# Adafruit_IS31FL3731_STEMMA_QT.net
KiCad netlist of a schematic drawn in EAGLE
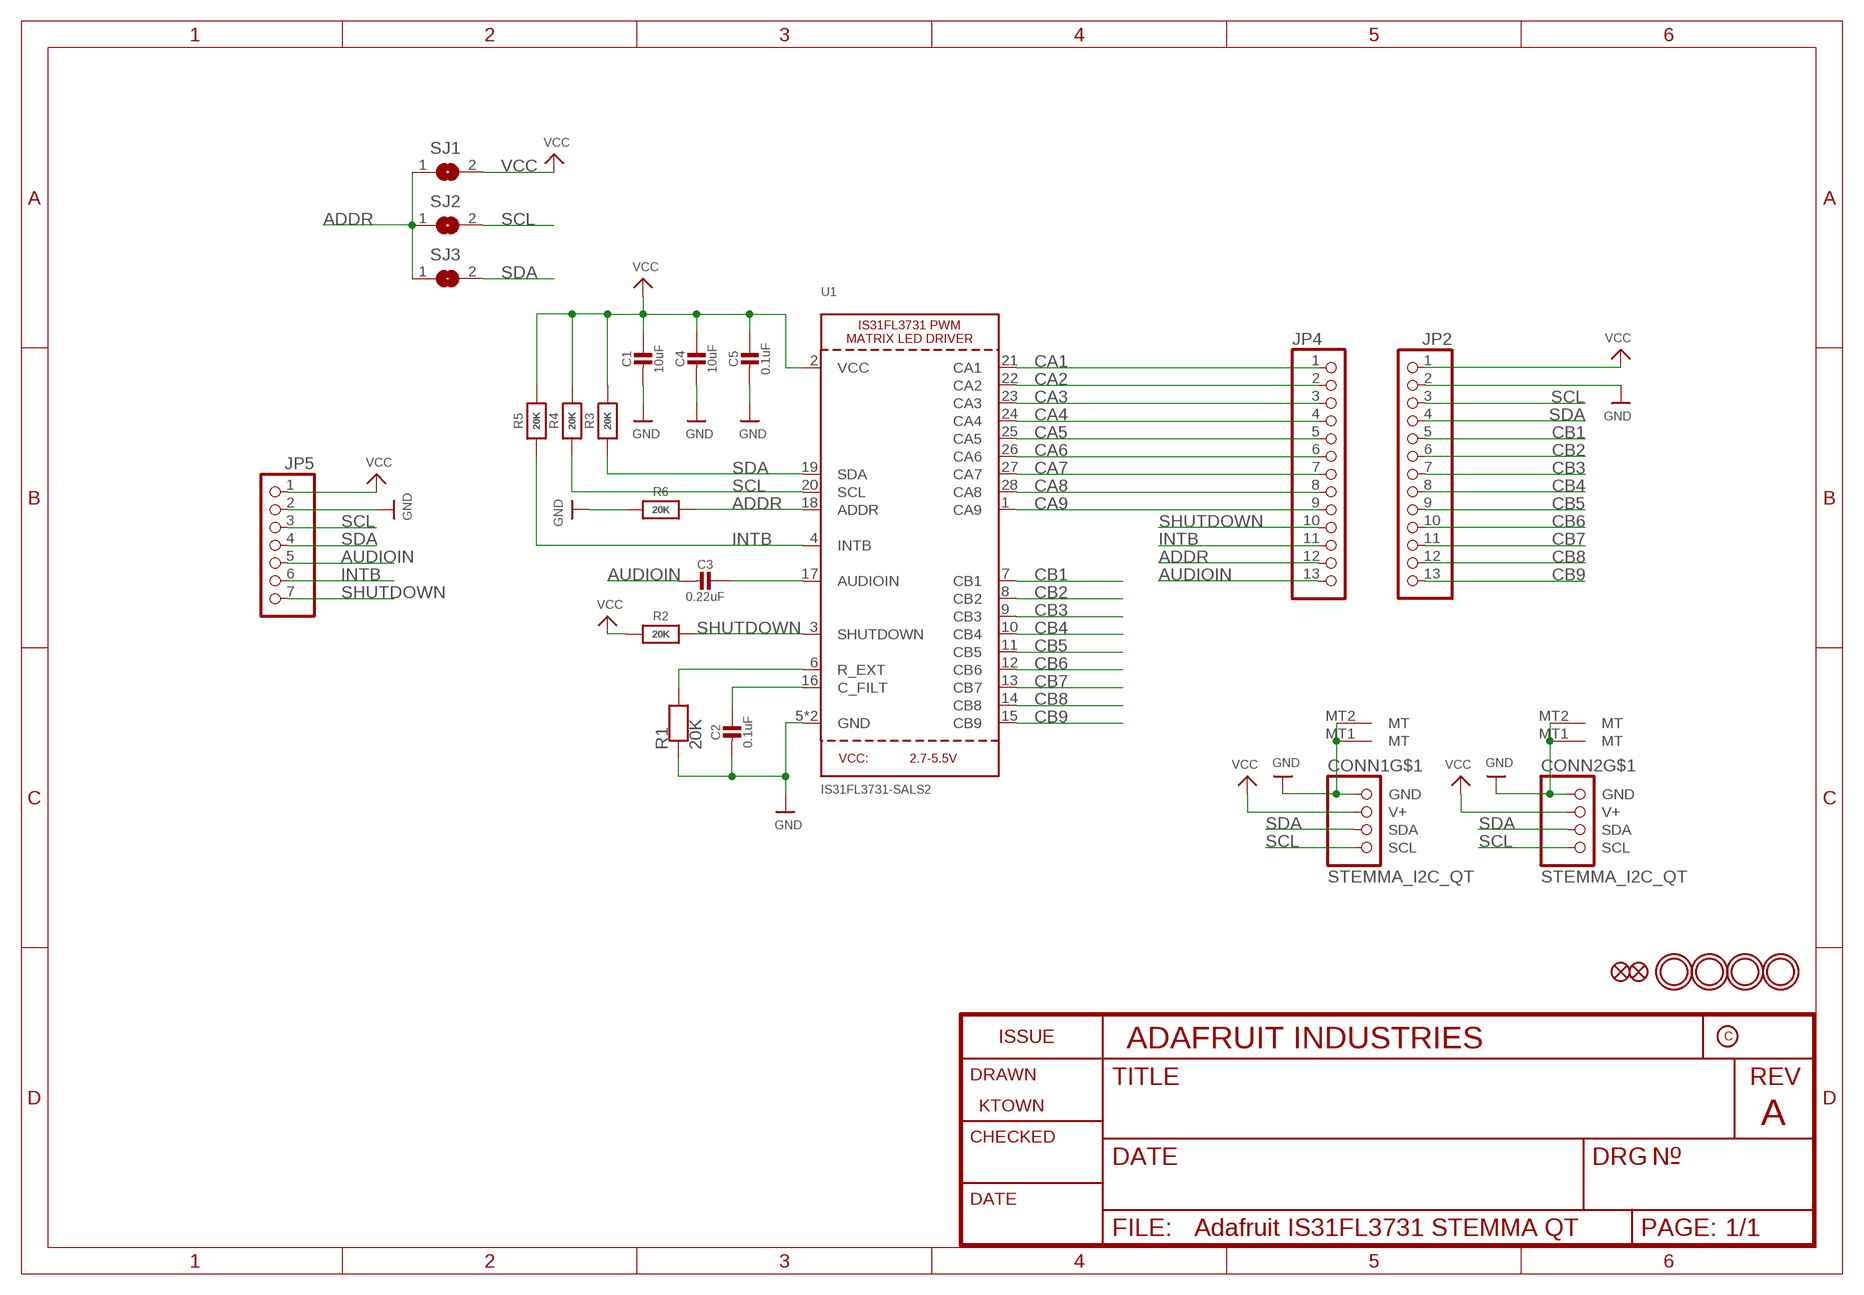
[diagram p0: schematic, sheet 1]

(export (version "E")
  (design (tool "Eeschema 10.0.6"))
  (components
    (comp (ref "C1")
      (value "10uF")
      (footprint "eagle-import:0805-NO")
      (libsource (lib "eagle-import") (part "CAP_CERAMIC0805-NOOUTLINE"))
    )
    (comp (ref "C2")
      (value "0.1uF")
      (footprint "eagle-import:0603-NO")
      (libsource (lib "eagle-import") (part "CAP_CERAMIC0603_NO"))
    )
    (comp (ref "C3")
      (value "0.22uF")
      (footprint "eagle-import:0603-NO")
      (libsource (lib "eagle-import") (part "CAP_CERAMIC0603_NO"))
    )
    (comp (ref "C4")
      (value "10uF")
      (footprint "eagle-import:0805-NO")
      (libsource (lib "eagle-import") (part "CAP_CERAMIC0805-NOOUTLINE"))
    )
    (comp (ref "C5")
      (value "0.1uF")
      (footprint "eagle-import:0603-NO")
      (libsource (lib "eagle-import") (part "CAP_CERAMIC0603_NO"))
    )
    (comp (ref "CONN1")
      (value "STEMMA_I2C_QT")
      (footprint "eagle-import:JST_SH4")
      (libsource (lib "eagle-import") (part "STEMMA_I2C_QT"))
    )
    (comp (ref "CONN2")
      (value "STEMMA_I2C_QT")
      (footprint "eagle-import:JST_SH4")
      (libsource (lib "eagle-import") (part "STEMMA_I2C_QT"))
    )
    (comp (ref "FID1")
      (value "FIDUCIAL_1MM")
      (footprint "eagle-import:FIDUCIAL_1MM")
      (libsource (lib "eagle-import") (part "FIDUCIAL_1MM"))
    )
    (comp (ref "FID2")
      (value "FIDUCIAL_1MM")
      (footprint "eagle-import:FIDUCIAL_1MM")
      (libsource (lib "eagle-import") (part "FIDUCIAL_1MM"))
    )
    (comp (ref "JP2")
      (value "HEADER-1X13")
      (footprint "eagle-import:1X13_ROUND_70")
      (libsource (lib "eagle-import") (part "HEADER-1X13"))
    )
    (comp (ref "JP4")
      (value "HEADER-1X13")
      (footprint "eagle-import:1X13_ROUND_70")
      (libsource (lib "eagle-import") (part "HEADER-1X13"))
    )
    (comp (ref "JP5")
      (value "HEADER-1X7THICKER")
      (footprint "eagle-import:1X07_ROUND_76")
      (libsource (lib "eagle-import") (part "HEADER-1X7THICKER"))
    )
    (comp (ref "R1")
      (value "20K")
      (footprint "eagle-import:0603-THM")
      (libsource (lib "eagle-import") (part "RESISTOR_0603THM"))
    )
    (comp (ref "R2")
      (value "20K")
      (footprint "eagle-import:0603-NO")
      (libsource (lib "eagle-import") (part "RESISTOR_0603_NOOUT"))
    )
    (comp (ref "R3")
      (value "20K")
      (footprint "eagle-import:0603-NO")
      (libsource (lib "eagle-import") (part "RESISTOR_0603_NOOUT"))
    )
    (comp (ref "R4")
      (value "20K")
      (footprint "eagle-import:0603-NO")
      (libsource (lib "eagle-import") (part "RESISTOR_0603_NOOUT"))
    )
    (comp (ref "R5")
      (value "20K")
      (footprint "eagle-import:0603-NO")
      (libsource (lib "eagle-import") (part "RESISTOR_0603_NOOUT"))
    )
    (comp (ref "R6")
      (value "20K")
      (footprint "eagle-import:0603-NO")
      (libsource (lib "eagle-import") (part "RESISTOR_0603_NOOUT"))
    )
    (comp (ref "SJ1")
      (value "SOLDERJUMPER")
      (footprint "eagle-import:SOLDERJUMPER_ARROW_NOPASTE")
      (libsource (lib "eagle-import") (part "SOLDERJUMPER"))
    )
    (comp (ref "SJ2")
      (value "SOLDERJUMPER")
      (footprint "eagle-import:SOLDERJUMPER_ARROW_NOPASTE")
      (libsource (lib "eagle-import") (part "SOLDERJUMPER"))
    )
    (comp (ref "SJ3")
      (value "SOLDERJUMPER")
      (footprint "eagle-import:SOLDERJUMPER_ARROW_NOPASTE")
      (libsource (lib "eagle-import") (part "SOLDERJUMPER"))
    )
    (comp (ref "U$3")
      (value "MOUNTINGHOLE2.5")
      (footprint "eagle-import:MOUNTINGHOLE_2.5_PLATED")
      (libsource (lib "eagle-import") (part "MOUNTINGHOLE2.5"))
    )
    (comp (ref "U$4")
      (value "MOUNTINGHOLE2.5")
      (footprint "eagle-import:MOUNTINGHOLE_2.5_PLATED")
      (libsource (lib "eagle-import") (part "MOUNTINGHOLE2.5"))
    )
    (comp (ref "U$5")
      (value "MOUNTINGHOLE2.5")
      (footprint "eagle-import:MOUNTINGHOLE_2.5_PLATED")
      (libsource (lib "eagle-import") (part "MOUNTINGHOLE2.5"))
    )
    (comp (ref "U$6")
      (value "MOUNTINGHOLE2.5")
      (footprint "eagle-import:MOUNTINGHOLE_2.5_PLATED")
      (libsource (lib "eagle-import") (part "MOUNTINGHOLE2.5"))
    )
    (comp (ref "U1")
      (value "IS31FL3731-SALS2")
      (footprint "eagle-import:QFN28_4MM_0.4MM")
      (libsource (lib "eagle-import") (part "IS31FL3731QFN"))
    )
  )
  (nets
    (net (code "1") (name "/ADDR") (class "Default")
      (node (ref "JP4") (pin "12") (pinfunction "12_12") (pintype "passive"))
      (node (ref "R6") (pin "2") (pinfunction "2_2") (pintype "passive"))
      (node (ref "SJ1") (pin "1") (pinfunction "1_1") (pintype "passive"))
      (node (ref "SJ2") (pin "1") (pinfunction "1_1") (pintype "passive"))
      (node (ref "SJ3") (pin "1") (pinfunction "1_1") (pintype "passive"))
      (node (ref "U1") (pin "18") (pinfunction "ADDR_18") (pintype "bidirectional"))
    )
    (net (code "2") (name "/AUDIOIN") (class "Default")
      (node (ref "C3") (pin "2") (pinfunction "2_2") (pintype "passive"))
      (node (ref "JP4") (pin "13") (pinfunction "13_13") (pintype "passive"))
      (node (ref "JP5") (pin "5") (pinfunction "5_5") (pintype "passive"))
    )
    (net (code "3") (name "/CA1") (class "Default")
      (node (ref "JP4") (pin "1") (pinfunction "1_1") (pintype "passive"))
      (node (ref "U1") (pin "21") (pinfunction "CA1_21") (pintype "bidirectional"))
    )
    (net (code "4") (name "/CA2") (class "Default")
      (node (ref "JP4") (pin "2") (pinfunction "2_2") (pintype "passive"))
      (node (ref "U1") (pin "22") (pinfunction "CA2_22") (pintype "bidirectional"))
    )
    (net (code "5") (name "/CA3") (class "Default")
      (node (ref "JP4") (pin "3") (pinfunction "3_3") (pintype "passive"))
      (node (ref "U1") (pin "23") (pinfunction "CA3_23") (pintype "bidirectional"))
    )
    (net (code "6") (name "/CA4") (class "Default")
      (node (ref "JP4") (pin "4") (pinfunction "4_4") (pintype "passive"))
      (node (ref "U1") (pin "24") (pinfunction "CA4_24") (pintype "bidirectional"))
    )
    (net (code "7") (name "/CA5") (class "Default")
      (node (ref "JP4") (pin "5") (pinfunction "5_5") (pintype "passive"))
      (node (ref "U1") (pin "25") (pinfunction "CA5_25") (pintype "bidirectional"))
    )
    (net (code "8") (name "/CA6") (class "Default")
      (node (ref "JP4") (pin "6") (pinfunction "6_6") (pintype "passive"))
      (node (ref "U1") (pin "26") (pinfunction "CA6_26") (pintype "bidirectional"))
    )
    (net (code "9") (name "/CA7") (class "Default")
      (node (ref "JP4") (pin "7") (pinfunction "7_7") (pintype "passive"))
      (node (ref "U1") (pin "27") (pinfunction "CA7_27") (pintype "bidirectional"))
    )
    (net (code "10") (name "/CA8") (class "Default")
      (node (ref "JP4") (pin "8") (pinfunction "8_8") (pintype "passive"))
      (node (ref "U1") (pin "28") (pinfunction "CA8_28") (pintype "bidirectional"))
    )
    (net (code "11") (name "/CA9") (class "Default")
      (node (ref "JP4") (pin "9") (pinfunction "9_9") (pintype "passive"))
      (node (ref "U1") (pin "1") (pinfunction "CA9_1") (pintype "bidirectional"))
    )
    (net (code "12") (name "/CB1") (class "Default")
      (node (ref "JP2") (pin "5") (pinfunction "5_5") (pintype "passive"))
      (node (ref "U1") (pin "7") (pinfunction "CB1_7") (pintype "bidirectional"))
    )
    (net (code "13") (name "/CB2") (class "Default")
      (node (ref "JP2") (pin "6") (pinfunction "6_6") (pintype "passive"))
      (node (ref "U1") (pin "8") (pinfunction "CB2_8") (pintype "bidirectional"))
    )
    (net (code "14") (name "/CB3") (class "Default")
      (node (ref "JP2") (pin "7") (pinfunction "7_7") (pintype "passive"))
      (node (ref "U1") (pin "9") (pinfunction "CB3_9") (pintype "bidirectional"))
    )
    (net (code "15") (name "/CB4") (class "Default")
      (node (ref "JP2") (pin "8") (pinfunction "8_8") (pintype "passive"))
      (node (ref "U1") (pin "10") (pinfunction "CB4_10") (pintype "bidirectional"))
    )
    (net (code "16") (name "/CB5") (class "Default")
      (node (ref "JP2") (pin "9") (pinfunction "9_9") (pintype "passive"))
      (node (ref "U1") (pin "11") (pinfunction "CB5_11") (pintype "bidirectional"))
    )
    (net (code "17") (name "/CB6") (class "Default")
      (node (ref "JP2") (pin "10") (pinfunction "10_10") (pintype "passive"))
      (node (ref "U1") (pin "12") (pinfunction "CB6_12") (pintype "bidirectional"))
    )
    (net (code "18") (name "/CB7") (class "Default")
      (node (ref "JP2") (pin "11") (pinfunction "11_11") (pintype "passive"))
      (node (ref "U1") (pin "13") (pinfunction "CB7_13") (pintype "bidirectional"))
    )
    (net (code "19") (name "/CB8") (class "Default")
      (node (ref "JP2") (pin "12") (pinfunction "12_12") (pintype "passive"))
      (node (ref "U1") (pin "14") (pinfunction "CB8_14") (pintype "bidirectional"))
    )
    (net (code "20") (name "/CB9") (class "Default")
      (node (ref "JP2") (pin "13") (pinfunction "13_13") (pintype "passive"))
      (node (ref "U1") (pin "15") (pinfunction "CB9_15") (pintype "bidirectional"))
    )
    (net (code "21") (name "/INTB") (class "Default")
      (node (ref "JP4") (pin "11") (pinfunction "11_11") (pintype "passive"))
      (node (ref "JP5") (pin "6") (pinfunction "6_6") (pintype "passive"))
      (node (ref "R5") (pin "1") (pinfunction "1_1") (pintype "passive"))
      (node (ref "U1") (pin "4") (pinfunction "INTB_4") (pintype "output"))
    )
    (net (code "22") (name "/SCL") (class "Default")
      (node (ref "CONN1") (pin "4") (pinfunction "SCL_4") (pintype "passive"))
      (node (ref "CONN2") (pin "4") (pinfunction "SCL_4") (pintype "passive"))
      (node (ref "JP2") (pin "3") (pinfunction "3_3") (pintype "passive"))
      (node (ref "JP5") (pin "3") (pinfunction "3_3") (pintype "passive"))
      (node (ref "R4") (pin "1") (pinfunction "1_1") (pintype "passive"))
      (node (ref "SJ2") (pin "2") (pinfunction "2_2") (pintype "passive"))
      (node (ref "U1") (pin "20") (pinfunction "SCL_20") (pintype "bidirectional"))
    )
    (net (code "23") (name "/SDA") (class "Default")
      (node (ref "CONN1") (pin "3") (pinfunction "SDA_3") (pintype "passive"))
      (node (ref "CONN2") (pin "3") (pinfunction "SDA_3") (pintype "passive"))
      (node (ref "JP2") (pin "4") (pinfunction "4_4") (pintype "passive"))
      (node (ref "JP5") (pin "4") (pinfunction "4_4") (pintype "passive"))
      (node (ref "R3") (pin "1") (pinfunction "1_1") (pintype "passive"))
      (node (ref "SJ3") (pin "2") (pinfunction "2_2") (pintype "passive"))
      (node (ref "U1") (pin "19") (pinfunction "SDA_19") (pintype "bidirectional"))
    )
    (net (code "24") (name "/SHUTDOWN") (class "Default")
      (node (ref "JP4") (pin "10") (pinfunction "10_10") (pintype "passive"))
      (node (ref "JP5") (pin "7") (pinfunction "7_7") (pintype "passive"))
      (node (ref "R2") (pin "2") (pinfunction "2_2") (pintype "passive"))
      (node (ref "U1") (pin "3") (pinfunction "SHUTDOWN_3") (pintype "input"))
    )
    (net (code "25") (name "GND") (class "Default")
      (node (ref "C1") (pin "2") (pinfunction "2_2") (pintype "passive"))
      (node (ref "C2") (pin "2") (pinfunction "2_2") (pintype "passive"))
      (node (ref "C4") (pin "2") (pinfunction "2_2") (pintype "passive"))
      (node (ref "C5") (pin "2") (pinfunction "2_2") (pintype "passive"))
      (node (ref "CONN1") (pin "1") (pinfunction "GND_1") (pintype "passive"))
      (node (ref "CONN1") (pin "MT1") (pinfunction "MT_MT1") (pintype "bidirectional"))
      (node (ref "CONN1") (pin "MT2") (pinfunction "MT_MT2") (pintype "bidirectional"))
      (node (ref "CONN2") (pin "1") (pinfunction "GND_1") (pintype "passive"))
      (node (ref "CONN2") (pin "MT1") (pinfunction "MT_MT1") (pintype "bidirectional"))
      (node (ref "CONN2") (pin "MT2") (pinfunction "MT_MT2") (pintype "bidirectional"))
      (node (ref "JP2") (pin "2") (pinfunction "2_2") (pintype "passive"))
      (node (ref "JP5") (pin "2") (pinfunction "2_2") (pintype "passive"))
      (node (ref "R1") (pin "1") (pinfunction "1_1") (pintype "passive"))
      (node (ref "R1") (pin "11") (pinfunction "1_11") (pintype "passive"))
      (node (ref "R6") (pin "1") (pinfunction "1_1") (pintype "passive"))
      (node (ref "U1") (pin "5") (pinfunction "GND_5") (pintype "power_in"))
      (node (ref "U1") (pin "THERMAL") (pinfunction "GND_THERMAL") (pintype "power_in"))
    )
    (net (code "26") (name "Net-(U1-AUDIOIN)") (class "Default")
      (node (ref "C3") (pin "1") (pinfunction "1_1") (pintype "passive"))
      (node (ref "U1") (pin "17") (pinfunction "AUDIOIN_17") (pintype "input"))
    )
    (net (code "27") (name "Net-(U1-C_FILT)") (class "Default")
      (node (ref "C2") (pin "1") (pinfunction "1_1") (pintype "passive"))
      (node (ref "U1") (pin "16") (pinfunction "C_FILT_16") (pintype "bidirectional"))
    )
    (net (code "28") (name "Net-(U1-R_EXT)") (class "Default")
      (node (ref "R1") (pin "2") (pinfunction "2_2") (pintype "passive"))
      (node (ref "R1") (pin "22") (pinfunction "2_22") (pintype "passive"))
      (node (ref "U1") (pin "6") (pinfunction "R_EXT_6") (pintype "bidirectional"))
    )
    (net (code "29") (name "VCC") (class "Default")
      (node (ref "C1") (pin "1") (pinfunction "1_1") (pintype "passive"))
      (node (ref "C4") (pin "1") (pinfunction "1_1") (pintype "passive"))
      (node (ref "C5") (pin "1") (pinfunction "1_1") (pintype "passive"))
      (node (ref "CONN1") (pin "2") (pinfunction "V+_2") (pintype "passive"))
      (node (ref "CONN2") (pin "2") (pinfunction "V+_2") (pintype "passive"))
      (node (ref "JP2") (pin "1") (pinfunction "1_1") (pintype "passive"))
      (node (ref "JP5") (pin "1") (pinfunction "1_1") (pintype "passive"))
      (node (ref "R2") (pin "1") (pinfunction "1_1") (pintype "passive"))
      (node (ref "R3") (pin "2") (pinfunction "2_2") (pintype "passive"))
      (node (ref "R4") (pin "2") (pinfunction "2_2") (pintype "passive"))
      (node (ref "R5") (pin "2") (pinfunction "2_2") (pintype "passive"))
      (node (ref "SJ1") (pin "2") (pinfunction "2_2") (pintype "passive"))
      (node (ref "U1") (pin "2") (pinfunction "VCC_2") (pintype "power_in"))
    )
  )
)
